# 02_HDMI_RX.net
KiCad netlist of a schematic drawn in Altium Designer
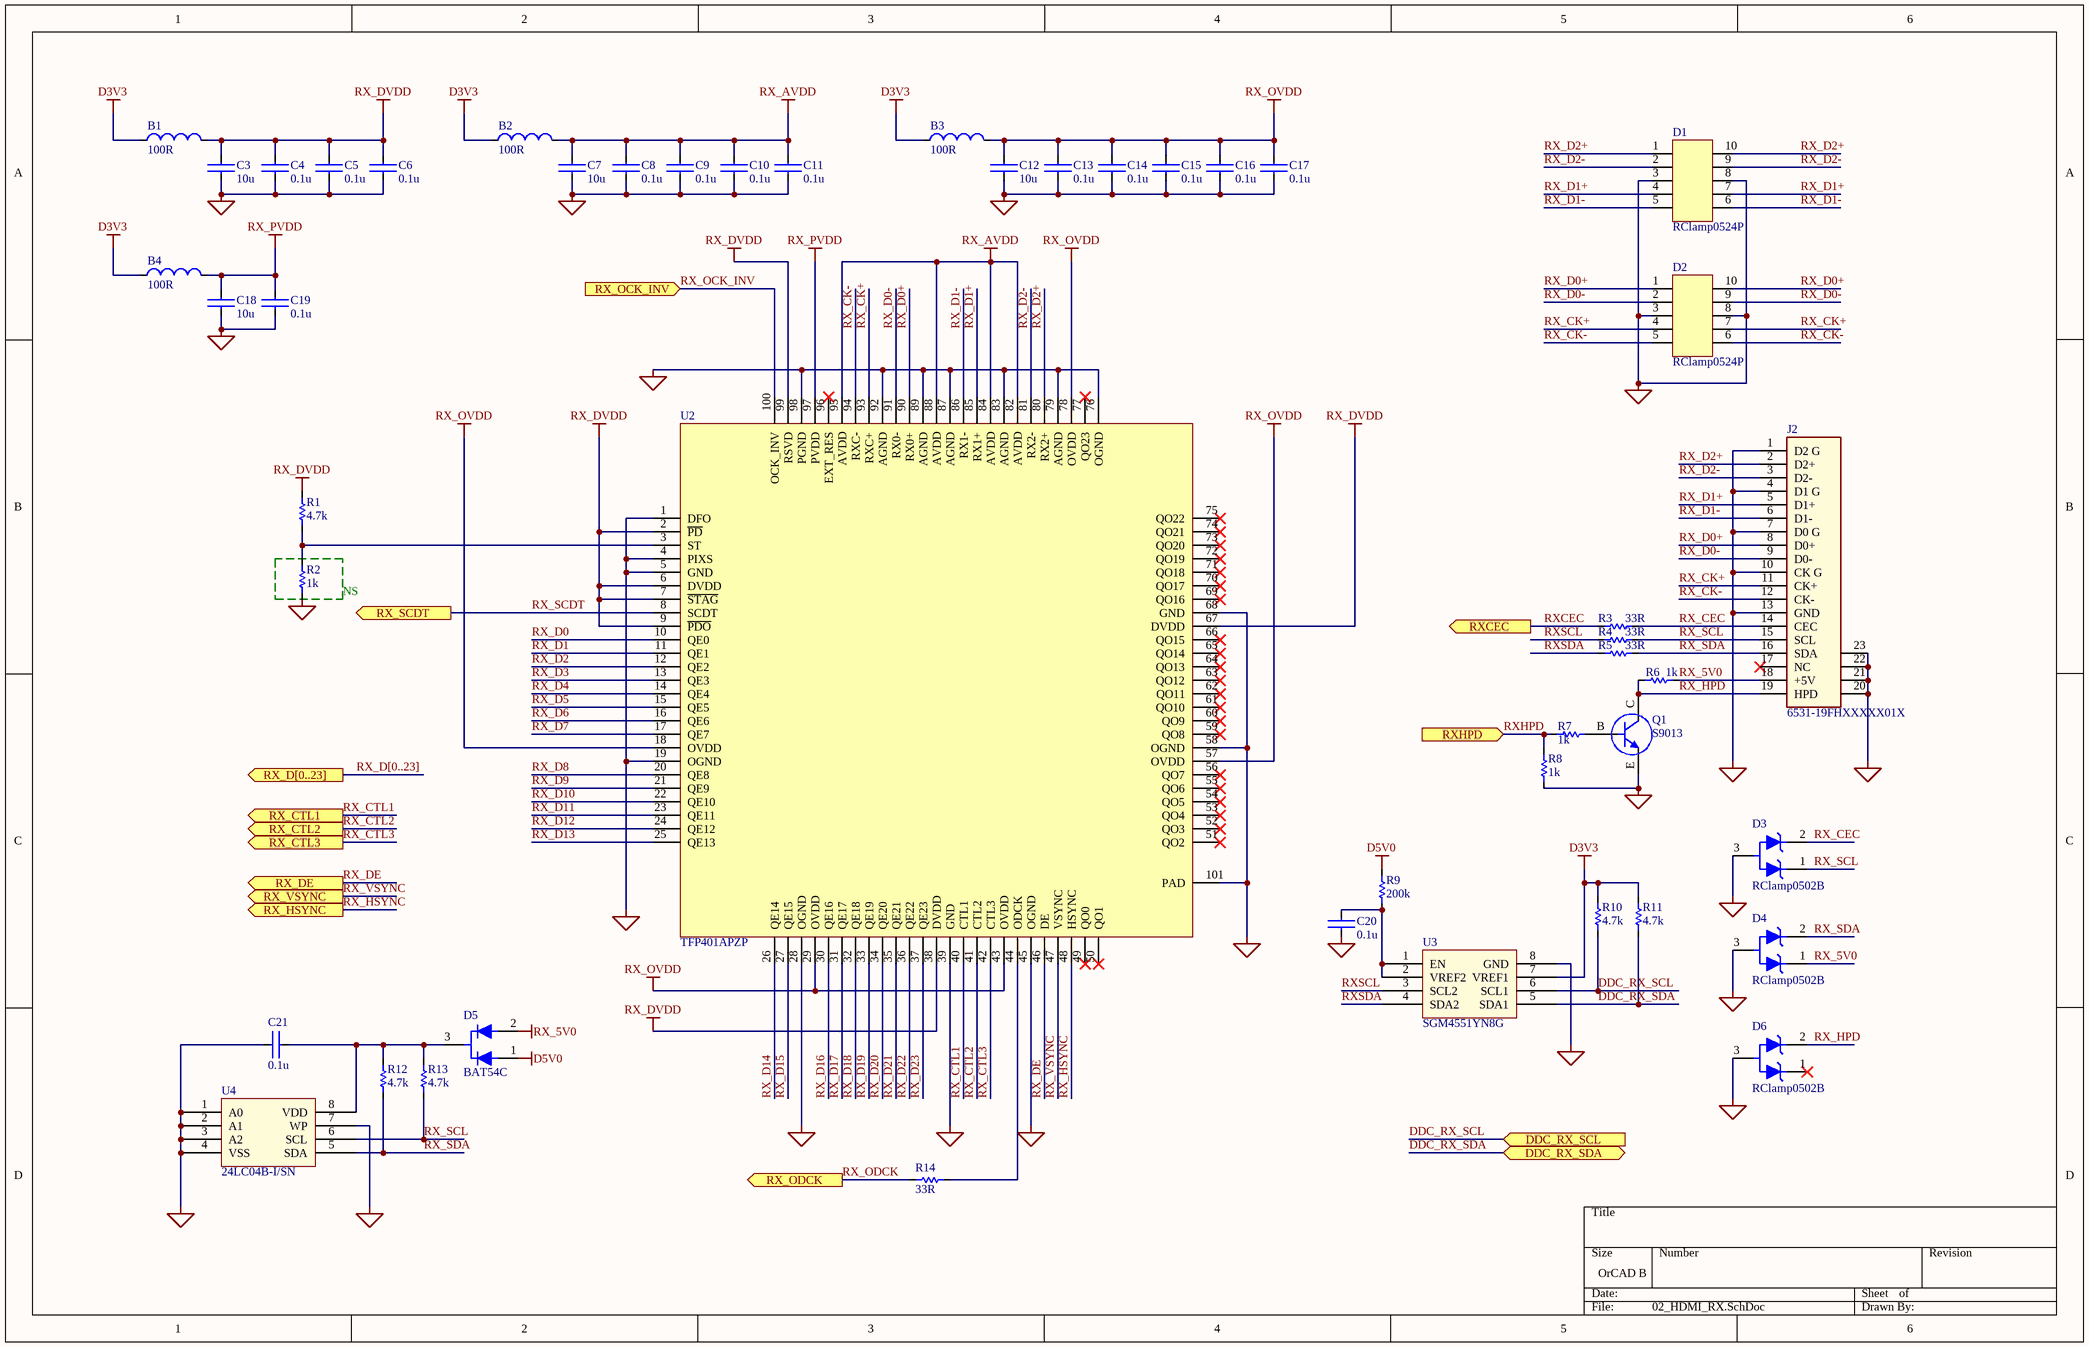
[diagram p0: 02_HDMI_RX.SchDoc]

(export (version "E")
  (design (tool "Eeschema 10.0.6"))
  (components
    (comp (ref "B1")
      (value "100R")
      (footprint "INDC1608X09N_B0603_TAIYO")
      (description "Bead,100R,2500mA,0.035ohm,0603")
      (libsource (lib "AD15_libpkg") (part "FBMH1608HM101-T"))
    )
    (comp (ref "B2")
      (value "100R")
      (footprint "INDC1608X09N_B0603_TAIYO")
      (description "Bead,100R,2500mA,0.035ohm,0603")
      (libsource (lib "AD15_libpkg") (part "FBMH1608HM101-T"))
    )
    (comp (ref "B3")
      (value "100R")
      (footprint "INDC1608X09N_B0603_TAIYO")
      (description "Bead,100R,2500mA,0.035ohm,0603")
      (libsource (lib "AD15_libpkg") (part "FBMH1608HM101-T"))
    )
    (comp (ref "B4")
      (value "100R")
      (footprint "INDC1608X09N_B0603_TAIYO")
      (description "Bead,100R,2500mA,0.035ohm,0603")
      (libsource (lib "AD15_libpkg") (part "FBMH1608HM101-T"))
    )
    (comp (ref "C3")
      (value "10u")
      (footprint "CAPC1608X09N_C0603")
      (description "CAP,Ceramic,X7R,10%,6.3V,10uF,0603")
      (libsource (lib "C0603") (part "CAP113"))
    )
    (comp (ref "C4")
      (value "0.1u")
      (footprint "C0402")
      (description "CAP,Ceramic,X7R,10%,16V,0.1uF,0402")
      (libsource (lib "C0402") (part "CAP011"))
    )
    (comp (ref "C5")
      (value "0.1u")
      (footprint "C0402")
      (description "CAP,Ceramic,X7R,10%,16V,0.1uF,0402")
      (libsource (lib "C0402") (part "CAP011"))
    )
    (comp (ref "C6")
      (value "0.1u")
      (footprint "C0402")
      (description "CAP,Ceramic,X7R,10%,16V,0.1uF,0402")
      (libsource (lib "C0402") (part "CAP011"))
    )
    (comp (ref "C7")
      (value "10u")
      (footprint "CAPC1608X09N_C0603")
      (description "CAP,Ceramic,X7R,10%,6.3V,10uF,0603")
      (libsource (lib "C0603") (part "CAP113"))
    )
    (comp (ref "C8")
      (value "0.1u")
      (footprint "C0402")
      (description "CAP,Ceramic,X7R,10%,16V,0.1uF,0402")
      (libsource (lib "C0402") (part "CAP011"))
    )
    (comp (ref "C9")
      (value "0.1u")
      (footprint "C0402")
      (description "CAP,Ceramic,X7R,10%,16V,0.1uF,0402")
      (libsource (lib "C0402") (part "CAP011"))
    )
    (comp (ref "C10")
      (value "0.1u")
      (footprint "C0402")
      (description "CAP,Ceramic,X7R,10%,16V,0.1uF,0402")
      (libsource (lib "C0402") (part "CAP011"))
    )
    (comp (ref "C11")
      (value "0.1u")
      (footprint "C0402")
      (description "CAP,Ceramic,X7R,10%,16V,0.1uF,0402")
      (libsource (lib "C0402") (part "CAP011"))
    )
    (comp (ref "C12")
      (value "10u")
      (footprint "CAPC1608X09N_C0603")
      (description "CAP,Ceramic,X7R,10%,6.3V,10uF,0603")
      (libsource (lib "C0603") (part "CAP113"))
    )
    (comp (ref "C13")
      (value "0.1u")
      (footprint "C0402")
      (description "CAP,Ceramic,X7R,10%,16V,0.1uF,0402")
      (libsource (lib "C0402") (part "CAP011"))
    )
    (comp (ref "C14")
      (value "0.1u")
      (footprint "C0402")
      (description "CAP,Ceramic,X7R,10%,16V,0.1uF,0402")
      (libsource (lib "C0402") (part "CAP011"))
    )
    (comp (ref "C15")
      (value "0.1u")
      (footprint "C0402")
      (description "CAP,Ceramic,X7R,10%,16V,0.1uF,0402")
      (libsource (lib "C0402") (part "CAP011"))
    )
    (comp (ref "C16")
      (value "0.1u")
      (footprint "C0402")
      (description "CAP,Ceramic,X7R,10%,16V,0.1uF,0402")
      (libsource (lib "C0402") (part "CAP011"))
    )
    (comp (ref "C17")
      (value "0.1u")
      (footprint "C0402")
      (description "CAP,Ceramic,X7R,10%,16V,0.1uF,0402")
      (libsource (lib "C0402") (part "CAP011"))
    )
    (comp (ref "C18")
      (value "10u")
      (footprint "CAPC1608X09N_C0603")
      (description "CAP,Ceramic,X7R,10%,6.3V,10uF,0603")
      (libsource (lib "C0603") (part "CAP113"))
    )
    (comp (ref "C19")
      (value "0.1u")
      (footprint "C0402")
      (description "CAP,Ceramic,X7R,10%,16V,0.1uF,0402")
      (libsource (lib "C0402") (part "CAP011"))
    )
    (comp (ref "C20")
      (value "0.1u")
      (footprint "C0402")
      (description "CAP,Ceramic,X7R,10%,16V,0.1uF,0402")
      (libsource (lib "C0402") (part "CAP011"))
    )
    (comp (ref "C21")
      (value "0.1u")
      (footprint "C0402")
      (description "CAP,Ceramic,X7R,10%,16V,0.1uF,0402")
      (libsource (lib "C0402") (part "CAP011"))
    )
    (comp (ref "D1")
      (value "RClamp0524P")
      (footprint "SLP2510P8_RClamp0524P")
      (description "TVS array,0.3pF,5V,SLP2510P8")
      (libsource (lib "AD15_libpkg") (part "RClamp0524P"))
    )
    (comp (ref "D2")
      (value "RClamp0524P")
      (footprint "SLP2510P8_RClamp0524P")
      (description "TVS array,0.3pF,5V,SLP2510P8")
      (libsource (lib "AD15_libpkg") (part "RClamp0524P"))
    )
    (comp (ref "D3")
      (value "RClamp0502B")
      (footprint "SOTFL50P160X90-3N_RClamp0502B")
      (description "TVS array,1pF,5V,SC75")
      (libsource (lib "AD15_libpkg") (part "RClamp0502B"))
    )
    (comp (ref "D4")
      (value "RClamp0502B")
      (footprint "SOTFL50P160X90-3N_RClamp0502B")
      (description "TVS array,1pF,5V,SC75")
      (libsource (lib "AD15_libpkg") (part "RClamp0502B"))
    )
    (comp (ref "D5")
      (value "BAT54C")
      (footprint "SOT95P230X110-3N_SOT23_BAT54")
      (description "Schottky Double Diodes,30V,200mA,SOT23,a1a2k1k2")
      (libsource (lib "AD15_libpkg") (part "BAT54C"))
    )
    (comp (ref "D6")
      (value "RClamp0502B")
      (footprint "SOTFL50P160X90-3N_RClamp0502B")
      (description "TVS array,1pF,5V,SC75")
      (libsource (lib "AD15_libpkg") (part "RClamp0502B"))
    )
    (comp (ref "J2")
      (value "6531-19FHXXXXX01X")
      (footprint "6531-19FHXXXXX01X")
      (description "Header,HDMI type C,19-Pin,Right angle,0.4mm Pitch,SMD")
      (libsource (lib "AD15_schlib") (part "6531-19FHXXXXX01X"))
    )
    (comp (ref "Q1")
      (value "S9013")
      (footprint "SOT95P240X115-3N_JCET_TRANSISTOR")
      (description "TRANSISTOR,NPN,40V,500mA,SOT23")
      (libsource (lib "AD15_libpkg") (part "S9013"))
    )
    (comp (ref "R1")
      (value "4.7k")
      (footprint "R0402")
      (description "RES,4.7k,1%,1/16W,0402")
      (libsource (lib "R0402") (part "RES015"))
    )
    (comp (ref "R2")
      (value "1k")
      (footprint "R0402")
      (description "RES,1k,1%,1/16W,0402")
      (libsource (lib "R0402") (part "RES011"))
    )
    (comp (ref "R3")
      (value "33R")
      (footprint "R0402")
      (description "RES,33R,1%,1/16W,0402")
      (libsource (lib "R0402") (part "RES017"))
    )
    (comp (ref "R4")
      (value "33R")
      (footprint "R0402")
      (description "RES,33R,1%,1/16W,0402")
      (libsource (lib "R0402") (part "RES017"))
    )
    (comp (ref "R5")
      (value "33R")
      (footprint "R0402")
      (description "RES,33R,1%,1/16W,0402")
      (libsource (lib "R0402") (part "RES017"))
    )
    (comp (ref "R6")
      (value "1k")
      (footprint "R0402")
      (description "RES,1k,1%,1/16W,0402")
      (libsource (lib "R0402") (part "RES011"))
    )
    (comp (ref "R7")
      (value "1k")
      (footprint "R0402")
      (description "RES,1k,1%,1/16W,0402")
      (libsource (lib "R0402") (part "RES011"))
    )
    (comp (ref "R8")
      (value "1k")
      (footprint "R0402")
      (description "RES,1k,1%,1/16W,0402")
      (libsource (lib "R0402") (part "RES011"))
    )
    (comp (ref "R9")
      (value "200k")
      (footprint "R0402")
      (description "RES,200k,1%,1/16W,0402")
      (libsource (lib "R0402") (part "RES0117"))
    )
    (comp (ref "R10")
      (value "4.7k")
      (footprint "R0402")
      (description "RES,4.7k,1%,1/16W,0402")
      (libsource (lib "R0402") (part "RES015"))
    )
    (comp (ref "R11")
      (value "4.7k")
      (footprint "R0402")
      (description "RES,4.7k,1%,1/16W,0402")
      (libsource (lib "R0402") (part "RES015"))
    )
    (comp (ref "R12")
      (value "4.7k")
      (footprint "R0402")
      (description "RES,4.7k,1%,1/16W,0402")
      (libsource (lib "R0402") (part "RES015"))
    )
    (comp (ref "R13")
      (value "4.7k")
      (footprint "R0402")
      (description "RES,4.7k,1%,1/16W,0402")
      (libsource (lib "R0402") (part "RES015"))
    )
    (comp (ref "R14")
      (value "33R")
      (footprint "R0402")
      (description "RES,33R,1%,1/16W,0402")
      (libsource (lib "R0402") (part "RES017"))
    )
    (comp (ref "U2")
      (value "TFP401APZP")
      (footprint "TSQFP50P1600X1600X120_HS-101N_TFP401")
      (description "IC,PanelBus Digital Receiver,HTQFP100")
      (libsource (lib "AD15_libpkg") (part "TFP401A"))
    )
    (comp (ref "U3")
      (value "SGM4551YN8G")
      (footprint "TSOP65P280X125-8N_SGM4551")
      (description "IC,I2C-bus and SMBus voltage-level translator,SOT23-8")
      (libsource (lib "AD15_libpkg") (part "SGM4551YN8G"))
    )
    (comp (ref "U4")
      (value "24LC04B-I/SN")
      (footprint "SOIC127P600X175-8N_24LC04B")
      (description "IC,EEPROM,512X8bits,I2C,SOIC8")
      (libsource (lib "AD15_libpkg") (part "24LC04B_01"))
    )
  )
  (nets
    (net (code "1") (name "/DDC_RX_SCL") (class "Default")
      (node (ref "R10") (pin "1") (pinfunction "0_1") (pintype "passive"))
      (node (ref "U3") (pin "6") (pinfunction "SCL1_6") (pintype "passive"))
    )
    (net (code "2") (name "/DDC_RX_SDA") (class "Default")
      (node (ref "R11") (pin "1") (pinfunction "0_1") (pintype "passive"))
      (node (ref "U3") (pin "5") (pinfunction "SDA1_5") (pintype "passive"))
    )
    (net (code "3") (name "/RXCEC") (class "Default")
      (node (ref "R3") (pin "1") (pinfunction "0_1") (pintype "passive"))
    )
    (net (code "4") (name "/RXHPD") (class "Default")
      (node (ref "R7") (pin "2") (pinfunction "2_2") (pintype "passive"))
      (node (ref "R8") (pin "2") (pinfunction "2_2") (pintype "passive"))
    )
    (net (code "5") (name "/RXSCL") (class "Default")
      (node (ref "R4") (pin "1") (pinfunction "0_1") (pintype "passive"))
      (node (ref "U3") (pin "3") (pinfunction "SCL2_3") (pintype "passive"))
    )
    (net (code "6") (name "/RXSDA") (class "Default")
      (node (ref "R5") (pin "1") (pinfunction "0_1") (pintype "passive"))
      (node (ref "U3") (pin "4") (pinfunction "SDA2_4") (pintype "passive"))
    )
    (net (code "7") (name "/RX_CEC") (class "Default")
      (node (ref "D3") (pin "2") (pinfunction "1_2") (pintype "passive"))
      (node (ref "J2") (pin "14") (pinfunction "CEC_14") (pintype "passive"))
      (node (ref "R3") (pin "2") (pinfunction "2_2") (pintype "passive"))
    )
    (net (code "8") (name "/RX_CK+") (class "Default")
      (node (ref "D2") (pin "4") (pinfunction "3_4") (pintype "passive"))
      (node (ref "D2") (pin "7") (pinfunction "6_7") (pintype "passive"))
      (node (ref "J2") (pin "11") (pinfunction "CK+_11") (pintype "passive"))
      (node (ref "U2") (pin "93") (pinfunction "RXC+_93") (pintype "passive"))
    )
    (net (code "9") (name "/RX_CK-") (class "Default")
      (node (ref "D2") (pin "5") (pinfunction "4_5") (pintype "passive"))
      (node (ref "D2") (pin "6") (pinfunction "5_6") (pintype "passive"))
      (node (ref "J2") (pin "12") (pinfunction "CK-_12") (pintype "passive"))
      (node (ref "U2") (pin "94") (pinfunction "RXC-_94") (pintype "passive"))
    )
    (net (code "10") (name "/RX_CTL1") (class "Default")
      (node (ref "U2") (pin "40") (pinfunction "CTL1_40") (pintype "passive"))
    )
    (net (code "11") (name "/RX_CTL2") (class "Default")
      (node (ref "U2") (pin "41") (pinfunction "CTL2_41") (pintype "passive"))
    )
    (net (code "12") (name "/RX_CTL3") (class "Default")
      (node (ref "U2") (pin "42") (pinfunction "CTL3_42") (pintype "passive"))
    )
    (net (code "13") (name "/RX_D0") (class "Default")
      (node (ref "U2") (pin "10") (pinfunction "QE0_10") (pintype "passive"))
    )
    (net (code "14") (name "/RX_D0+") (class "Default")
      (node (ref "D2") (pin "1") (pinfunction "0_1") (pintype "passive"))
      (node (ref "D2") (pin "10") (pinfunction "9_10") (pintype "passive"))
      (node (ref "J2") (pin "8") (pinfunction "D0+_8") (pintype "passive"))
      (node (ref "U2") (pin "90") (pinfunction "RX0+_90") (pintype "passive"))
    )
    (net (code "15") (name "/RX_D0-") (class "Default")
      (node (ref "D2") (pin "2") (pinfunction "1_2") (pintype "passive"))
      (node (ref "D2") (pin "9") (pinfunction "8_9") (pintype "passive"))
      (node (ref "J2") (pin "9") (pinfunction "D0-_9") (pintype "passive"))
      (node (ref "U2") (pin "91") (pinfunction "RX0-_91") (pintype "passive"))
    )
    (net (code "16") (name "/RX_D1") (class "Default")
      (node (ref "U2") (pin "11") (pinfunction "QE1_11") (pintype "passive"))
    )
    (net (code "17") (name "/RX_D1+") (class "Default")
      (node (ref "D1") (pin "4") (pinfunction "3_4") (pintype "passive"))
      (node (ref "D1") (pin "7") (pinfunction "6_7") (pintype "passive"))
      (node (ref "J2") (pin "5") (pinfunction "D1+_5") (pintype "passive"))
      (node (ref "U2") (pin "85") (pinfunction "RX1+_85") (pintype "passive"))
    )
    (net (code "18") (name "/RX_D1-") (class "Default")
      (node (ref "D1") (pin "5") (pinfunction "4_5") (pintype "passive"))
      (node (ref "D1") (pin "6") (pinfunction "5_6") (pintype "passive"))
      (node (ref "J2") (pin "6") (pinfunction "D1-_6") (pintype "passive"))
      (node (ref "U2") (pin "86") (pinfunction "RX1-_86") (pintype "passive"))
    )
    (net (code "19") (name "/RX_D2") (class "Default")
      (node (ref "U2") (pin "12") (pinfunction "QE2_12") (pintype "passive"))
    )
    (net (code "20") (name "/RX_D2+") (class "Default")
      (node (ref "D1") (pin "1") (pinfunction "0_1") (pintype "passive"))
      (node (ref "D1") (pin "10") (pinfunction "9_10") (pintype "passive"))
      (node (ref "J2") (pin "2") (pinfunction "D2+_2") (pintype "passive"))
      (node (ref "U2") (pin "80") (pinfunction "RX2+_80") (pintype "passive"))
    )
    (net (code "21") (name "/RX_D2-") (class "Default")
      (node (ref "D1") (pin "2") (pinfunction "1_2") (pintype "passive"))
      (node (ref "D1") (pin "9") (pinfunction "8_9") (pintype "passive"))
      (node (ref "J2") (pin "3") (pinfunction "D2-_3") (pintype "passive"))
      (node (ref "U2") (pin "81") (pinfunction "RX2-_81") (pintype "passive"))
    )
    (net (code "22") (name "/RX_D3") (class "Default")
      (node (ref "U2") (pin "13") (pinfunction "QE3_13") (pintype "passive"))
    )
    (net (code "23") (name "/RX_D4") (class "Default")
      (node (ref "U2") (pin "14") (pinfunction "QE4_14") (pintype "passive"))
    )
    (net (code "24") (name "/RX_D5") (class "Default")
      (node (ref "U2") (pin "15") (pinfunction "QE5_15") (pintype "passive"))
    )
    (net (code "25") (name "/RX_D6") (class "Default")
      (node (ref "U2") (pin "16") (pinfunction "QE6_16") (pintype "passive"))
    )
    (net (code "26") (name "/RX_D7") (class "Default")
      (node (ref "U2") (pin "17") (pinfunction "QE7_17") (pintype "passive"))
    )
    (net (code "27") (name "/RX_D8") (class "Default")
      (node (ref "U2") (pin "20") (pinfunction "QE8_20") (pintype "passive"))
    )
    (net (code "28") (name "/RX_D9") (class "Default")
      (node (ref "U2") (pin "21") (pinfunction "QE9_21") (pintype "passive"))
    )
    (net (code "29") (name "/RX_D10") (class "Default")
      (node (ref "U2") (pin "22") (pinfunction "QE10_22") (pintype "passive"))
    )
    (net (code "30") (name "/RX_D11") (class "Default")
      (node (ref "U2") (pin "23") (pinfunction "QE11_23") (pintype "passive"))
    )
    (net (code "31") (name "/RX_D12") (class "Default")
      (node (ref "U2") (pin "24") (pinfunction "QE12_24") (pintype "passive"))
    )
    (net (code "32") (name "/RX_D13") (class "Default")
      (node (ref "U2") (pin "25") (pinfunction "QE13_25") (pintype "passive"))
    )
    (net (code "33") (name "/RX_D14") (class "Default")
      (node (ref "U2") (pin "26") (pinfunction "QE14_26") (pintype "passive"))
    )
    (net (code "34") (name "/RX_D15") (class "Default")
      (node (ref "U2") (pin "27") (pinfunction "QE15_27") (pintype "passive"))
    )
    (net (code "35") (name "/RX_D16") (class "Default")
      (node (ref "U2") (pin "30") (pinfunction "QE16_30") (pintype "passive"))
    )
    (net (code "36") (name "/RX_D17") (class "Default")
      (node (ref "U2") (pin "31") (pinfunction "QE17_31") (pintype "passive"))
    )
    (net (code "37") (name "/RX_D18") (class "Default")
      (node (ref "U2") (pin "32") (pinfunction "QE18_32") (pintype "passive"))
    )
    (net (code "38") (name "/RX_D19") (class "Default")
      (node (ref "U2") (pin "33") (pinfunction "QE19_33") (pintype "passive"))
    )
    (net (code "39") (name "/RX_D20") (class "Default")
      (node (ref "U2") (pin "34") (pinfunction "QE20_34") (pintype "passive"))
    )
    (net (code "40") (name "/RX_D21") (class "Default")
      (node (ref "U2") (pin "35") (pinfunction "QE21_35") (pintype "passive"))
    )
    (net (code "41") (name "/RX_D22") (class "Default")
      (node (ref "U2") (pin "36") (pinfunction "QE22_36") (pintype "passive"))
    )
    (net (code "42") (name "/RX_D23") (class "Default")
      (node (ref "U2") (pin "37") (pinfunction "QE23_37") (pintype "passive"))
    )
    (net (code "43") (name "/RX_DE") (class "Default")
      (node (ref "U2") (pin "46") (pinfunction "DE_46") (pintype "passive"))
    )
    (net (code "45") (name "/RX_HPD") (class "Default")
      (node (ref "D6") (pin "2") (pinfunction "1_2") (pintype "passive"))
      (node (ref "J2") (pin "19") (pinfunction "HPD_19") (pintype "passive"))
      (node (ref "Q1") (pin "C") (pinfunction "C_C") (pintype "passive"))
      (node (ref "R6") (pin "2") (pinfunction "2_2") (pintype "passive"))
    )
    (net (code "46") (name "/RX_HSYNC") (class "Default")
      (node (ref "U2") (pin "48") (pinfunction "HSYNC_48") (pintype "passive"))
    )
    (net (code "47") (name "/RX_OCK_INV") (class "Default")
      (node (ref "U2") (pin "100") (pinfunction "OCK_INV_100") (pintype "passive"))
    )
    (net (code "48") (name "/RX_ODCK") (class "Default")
      (node (ref "R14") (pin "1") (pinfunction "0_1") (pintype "passive"))
    )
    (net (code "49") (name "/RX_SCDT") (class "Default")
      (node (ref "U2") (pin "8") (pinfunction "SCDT_8") (pintype "passive"))
    )
    (net (code "50") (name "/RX_SCL") (class "Default")
      (node (ref "D3") (pin "1") (pinfunction "0_1") (pintype "passive"))
      (node (ref "J2") (pin "15") (pinfunction "SCL_15") (pintype "passive"))
      (node (ref "R13") (pin "1") (pinfunction "0_1") (pintype "passive"))
      (node (ref "R4") (pin "2") (pinfunction "2_2") (pintype "passive"))
      (node (ref "U4") (pin "6") (pinfunction "SCL_6") (pintype "passive"))
    )
    (net (code "51") (name "/RX_SDA") (class "Default")
      (node (ref "D4") (pin "2") (pinfunction "1_2") (pintype "passive"))
      (node (ref "J2") (pin "16") (pinfunction "SDA_16") (pintype "passive"))
      (node (ref "R12") (pin "1") (pinfunction "0_1") (pintype "passive"))
      (node (ref "R5") (pin "2") (pinfunction "2_2") (pintype "passive"))
      (node (ref "U4") (pin "5") (pinfunction "SDA_5") (pintype "passive"))
    )
    (net (code "52") (name "/RX_VSYNC") (class "Default")
      (node (ref "U2") (pin "47") (pinfunction "VSYNC_47") (pintype "passive"))
    )
    (net (code "53") (name "D3V3") (class "Default")
      (node (ref "B1") (pin "2") (pinfunction "1_2") (pintype "passive"))
      (node (ref "B2") (pin "2") (pinfunction "1_2") (pintype "passive"))
      (node (ref "B3") (pin "2") (pinfunction "1_2") (pintype "passive"))
      (node (ref "B4") (pin "2") (pinfunction "1_2") (pintype "passive"))
      (node (ref "R10") (pin "2") (pinfunction "2_2") (pintype "passive"))
      (node (ref "R11") (pin "2") (pinfunction "2_2") (pintype "passive"))
      (node (ref "U3") (pin "7") (pinfunction "VREF1_7") (pintype "passive"))
    )
    (net (code "54") (name "D5V0") (class "Default")
      (node (ref "D5") (pin "1") (pinfunction "0_1") (pintype "passive"))
      (node (ref "R9") (pin "2") (pinfunction "2_2") (pintype "passive"))
    )
    (net (code "55") (name "GND") (class "Default")
      (node (ref "C10") (pin "2") (pinfunction "1_2") (pintype "passive"))
      (node (ref "C11") (pin "2") (pinfunction "1_2") (pintype "passive"))
      (node (ref "C12") (pin "2") (pinfunction "1_2") (pintype "passive"))
      (node (ref "C13") (pin "2") (pinfunction "1_2") (pintype "passive"))
      (node (ref "C14") (pin "2") (pinfunction "1_2") (pintype "passive"))
      (node (ref "C15") (pin "2") (pinfunction "1_2") (pintype "passive"))
      (node (ref "C16") (pin "2") (pinfunction "1_2") (pintype "passive"))
      (node (ref "C17") (pin "2") (pinfunction "1_2") (pintype "passive"))
      (node (ref "C18") (pin "2") (pinfunction "1_2") (pintype "passive"))
      (node (ref "C19") (pin "2") (pinfunction "1_2") (pintype "passive"))
      (node (ref "C20") (pin "2") (pinfunction "1_2") (pintype "passive"))
      (node (ref "C21") (pin "1") (pinfunction "0_1") (pintype "passive"))
      (node (ref "C3") (pin "2") (pinfunction "1_2") (pintype "passive"))
      (node (ref "C4") (pin "2") (pinfunction "1_2") (pintype "passive"))
      (node (ref "C5") (pin "2") (pinfunction "1_2") (pintype "passive"))
      (node (ref "C6") (pin "2") (pinfunction "1_2") (pintype "passive"))
      (node (ref "C7") (pin "2") (pinfunction "1_2") (pintype "passive"))
      (node (ref "C8") (pin "2") (pinfunction "1_2") (pintype "passive"))
      (node (ref "C9") (pin "2") (pinfunction "1_2") (pintype "passive"))
      (node (ref "D1") (pin "3") (pinfunction "2_3") (pintype "passive"))
      (node (ref "D1") (pin "8") (pinfunction "7_8") (pintype "passive"))
      (node (ref "D2") (pin "3") (pinfunction "2_3") (pintype "passive"))
      (node (ref "D2") (pin "8") (pinfunction "7_8") (pintype "passive"))
      (node (ref "D3") (pin "3") (pinfunction "2_3") (pintype "passive"))
      (node (ref "D4") (pin "3") (pinfunction "2_3") (pintype "passive"))
      (node (ref "D6") (pin "3") (pinfunction "2_3") (pintype "passive"))
      (node (ref "J2") (pin "1") (pinfunction "D2_G_1") (pintype "passive"))
      (node (ref "J2") (pin "10") (pinfunction "CK_G_10") (pintype "passive"))
      (node (ref "J2") (pin "13") (pinfunction "GND_13") (pintype "passive"))
      (node (ref "J2") (pin "20") (pinfunction "3_20") (pintype "passive"))
      (node (ref "J2") (pin "21") (pinfunction "4_21") (pintype "passive"))
      (node (ref "J2") (pin "22") (pinfunction "5_22") (pintype "passive"))
      (node (ref "J2") (pin "23") (pinfunction "6_23") (pintype "passive"))
      (node (ref "J2") (pin "4") (pinfunction "D1_G_4") (pintype "passive"))
      (node (ref "J2") (pin "7") (pinfunction "D0_G_7") (pintype "passive"))
      (node (ref "Q1") (pin "E") (pinfunction "E_E") (pintype "passive"))
      (node (ref "R2") (pin "1") (pinfunction "0_1") (pintype "passive"))
      (node (ref "R8") (pin "1") (pinfunction "0_1") (pintype "passive"))
      (node (ref "U2") (pin "1") (pinfunction "DFO_1") (pintype "passive"))
      (node (ref "U2") (pin "101") (pinfunction "PAD_101") (pintype "passive"))
      (node (ref "U2") (pin "19") (pinfunction "OGND_19") (pintype "passive"))
      (node (ref "U2") (pin "28") (pinfunction "OGND_28") (pintype "passive"))
      (node (ref "U2") (pin "39") (pinfunction "GND_39") (pintype "passive"))
      (node (ref "U2") (pin "4") (pinfunction "PIXS_4") (pintype "passive"))
      (node (ref "U2") (pin "45") (pinfunction "OGND_45") (pintype "passive"))
      (node (ref "U2") (pin "5") (pinfunction "GND_5") (pintype "passive"))
      (node (ref "U2") (pin "58") (pinfunction "OGND_58") (pintype "passive"))
      (node (ref "U2") (pin "68") (pinfunction "GND_68") (pintype "passive"))
      (node (ref "U2") (pin "76") (pinfunction "OGND_76") (pintype "passive"))
      (node (ref "U2") (pin "79") (pinfunction "AGND_79") (pintype "passive"))
      (node (ref "U2") (pin "83") (pinfunction "AGND_83") (pintype "passive"))
      (node (ref "U2") (pin "87") (pinfunction "AGND_87") (pintype "passive"))
      (node (ref "U2") (pin "89") (pinfunction "AGND_89") (pintype "passive"))
      (node (ref "U2") (pin "92") (pinfunction "AGND_92") (pintype "passive"))
      (node (ref "U2") (pin "98") (pinfunction "PGND_98") (pintype "passive"))
      (node (ref "U3") (pin "8") (pinfunction "GND_8") (pintype "passive"))
      (node (ref "U4") (pin "1") (pinfunction "A0_1") (pintype "passive"))
      (node (ref "U4") (pin "2") (pinfunction "A1_2") (pintype "passive"))
      (node (ref "U4") (pin "3") (pinfunction "A2_3") (pintype "passive"))
      (node (ref "U4") (pin "4") (pinfunction "VSS_4") (pintype "passive"))
      (node (ref "U4") (pin "7") (pinfunction "WP_7") (pintype "passive"))
    )
    (net (code "56") (name "Net-(C20-0)") (class "Default")
      (node (ref "C20") (pin "1") (pinfunction "0_1") (pintype "passive"))
      (node (ref "R9") (pin "1") (pinfunction "0_1") (pintype "passive"))
      (node (ref "U3") (pin "1") (pinfunction "EN_1") (pintype "passive"))
      (node (ref "U3") (pin "2") (pinfunction "VREF2_2") (pintype "passive"))
    )
    (net (code "57") (name "Net-(C21-1)") (class "Default")
      (node (ref "C21") (pin "2") (pinfunction "1_2") (pintype "passive"))
      (node (ref "D5") (pin "3") (pinfunction "2_3") (pintype "passive"))
      (node (ref "R12") (pin "2") (pinfunction "2_2") (pintype "passive"))
      (node (ref "R13") (pin "2") (pinfunction "2_2") (pintype "passive"))
      (node (ref "U4") (pin "8") (pinfunction "VDD_8") (pintype "passive"))
    )
    (net (code "58") (name "Net-(R1-0)") (class "Default")
      (node (ref "R1") (pin "1") (pinfunction "0_1") (pintype "passive"))
      (node (ref "R2") (pin "2") (pinfunction "2_2") (pintype "passive"))
      (node (ref "U2") (pin "3") (pinfunction "ST_3") (pintype "passive"))
    )
    (net (code "59") (name "Net-(R7-0)") (class "Default")
      (node (ref "Q1") (pin "B") (pinfunction "B_B") (pintype "passive"))
      (node (ref "R7") (pin "1") (pinfunction "0_1") (pintype "passive"))
    )
    (net (code "60") (name "Net-(U2-ODCK)") (class "Default")
      (node (ref "R14") (pin "2") (pinfunction "2_2") (pintype "passive"))
      (node (ref "U2") (pin "44") (pinfunction "ODCK_44") (pintype "passive"))
    )
    (net (code "61") (name "RX_5V0") (class "Default")
      (node (ref "D4") (pin "1") (pinfunction "0_1") (pintype "passive"))
      (node (ref "D5") (pin "2") (pinfunction "1_2") (pintype "passive"))
      (node (ref "J2") (pin "18") (pinfunction "+5V_18") (pintype "passive"))
      (node (ref "R6") (pin "1") (pinfunction "0_1") (pintype "passive"))
    )
    (net (code "62") (name "RX_AVDD") (class "Default")
      (node (ref "B2") (pin "1") (pinfunction "0_1") (pintype "passive"))
      (node (ref "C10") (pin "1") (pinfunction "0_1") (pintype "passive"))
      (node (ref "C11") (pin "1") (pinfunction "0_1") (pintype "passive"))
      (node (ref "C7") (pin "1") (pinfunction "0_1") (pintype "passive"))
      (node (ref "C8") (pin "1") (pinfunction "0_1") (pintype "passive"))
      (node (ref "C9") (pin "1") (pinfunction "0_1") (pintype "passive"))
      (node (ref "U2") (pin "82") (pinfunction "AVDD_82") (pintype "passive"))
      (node (ref "U2") (pin "84") (pinfunction "AVDD_84") (pintype "passive"))
      (node (ref "U2") (pin "88") (pinfunction "AVDD_88") (pintype "passive"))
      (node (ref "U2") (pin "95") (pinfunction "AVDD_95") (pintype "passive"))
    )
    (net (code "63") (name "RX_DVDD") (class "Default")
      (node (ref "B1") (pin "1") (pinfunction "0_1") (pintype "passive"))
      (node (ref "C3") (pin "1") (pinfunction "0_1") (pintype "passive"))
      (node (ref "C4") (pin "1") (pinfunction "0_1") (pintype "passive"))
      (node (ref "C5") (pin "1") (pinfunction "0_1") (pintype "passive"))
      (node (ref "C6") (pin "1") (pinfunction "0_1") (pintype "passive"))
      (node (ref "R1") (pin "2") (pinfunction "2_2") (pintype "passive"))
      (node (ref "U2") (pin "2") (pinfunction "~{PD}_2") (pintype "passive"))
      (node (ref "U2") (pin "38") (pinfunction "DVDD_38") (pintype "passive"))
      (node (ref "U2") (pin "6") (pinfunction "DVDD_6") (pintype "passive"))
      (node (ref "U2") (pin "67") (pinfunction "DVDD_67") (pintype "passive"))
      (node (ref "U2") (pin "7") (pinfunction "~{STAG}_7") (pintype "passive"))
      (node (ref "U2") (pin "9") (pinfunction "~{PDO}_9") (pintype "passive"))
      (node (ref "U2") (pin "99") (pinfunction "RSVD_99") (pintype "passive"))
    )
    (net (code "64") (name "RX_OVDD") (class "Default")
      (node (ref "B3") (pin "1") (pinfunction "0_1") (pintype "passive"))
      (node (ref "C12") (pin "1") (pinfunction "0_1") (pintype "passive"))
      (node (ref "C13") (pin "1") (pinfunction "0_1") (pintype "passive"))
      (node (ref "C14") (pin "1") (pinfunction "0_1") (pintype "passive"))
      (node (ref "C15") (pin "1") (pinfunction "0_1") (pintype "passive"))
      (node (ref "C16") (pin "1") (pinfunction "0_1") (pintype "passive"))
      (node (ref "C17") (pin "1") (pinfunction "0_1") (pintype "passive"))
      (node (ref "U2") (pin "18") (pinfunction "OVDD_18") (pintype "passive"))
      (node (ref "U2") (pin "29") (pinfunction "OVDD_29") (pintype "passive"))
      (node (ref "U2") (pin "43") (pinfunction "OVDD_43") (pintype "passive"))
      (node (ref "U2") (pin "57") (pinfunction "OVDD_57") (pintype "passive"))
      (node (ref "U2") (pin "78") (pinfunction "OVDD_78") (pintype "passive"))
    )
    (net (code "65") (name "RX_PVDD") (class "Default")
      (node (ref "B4") (pin "1") (pinfunction "0_1") (pintype "passive"))
      (node (ref "C18") (pin "1") (pinfunction "0_1") (pintype "passive"))
      (node (ref "C19") (pin "1") (pinfunction "0_1") (pintype "passive"))
      (node (ref "U2") (pin "97") (pinfunction "PVDD_97") (pintype "passive"))
    )
    (net (code "66") (name "unconnected-(D6-0-Pad1)") (class "Default")
      (node (ref "D6") (pin "1") (pinfunction "0_1") (pintype "passive+no_connect"))
    )
    (net (code "67") (name "unconnected-(J2-NC-Pad17)") (class "Default")
      (node (ref "J2") (pin "17") (pinfunction "NC_17") (pintype "passive+no_connect"))
    )
    (net (code "68") (name "unconnected-(U2-EXT_RES-Pad96)") (class "Default")
      (node (ref "U2") (pin "96") (pinfunction "EXT_RES_96") (pintype "passive+no_connect"))
    )
    (net (code "69") (name "unconnected-(U2-QO0-Pad49)") (class "Default")
      (node (ref "U2") (pin "49") (pinfunction "QO0_49") (pintype "passive+no_connect"))
    )
    (net (code "70") (name "unconnected-(U2-QO1-Pad50)") (class "Default")
      (node (ref "U2") (pin "50") (pinfunction "QO1_50") (pintype "passive+no_connect"))
    )
    (net (code "71") (name "unconnected-(U2-QO2-Pad51)") (class "Default")
      (node (ref "U2") (pin "51") (pinfunction "QO2_51") (pintype "passive+no_connect"))
    )
    (net (code "72") (name "unconnected-(U2-QO3-Pad52)") (class "Default")
      (node (ref "U2") (pin "52") (pinfunction "QO3_52") (pintype "passive+no_connect"))
    )
    (net (code "73") (name "unconnected-(U2-QO4-Pad53)") (class "Default")
      (node (ref "U2") (pin "53") (pinfunction "QO4_53") (pintype "passive+no_connect"))
    )
    (net (code "74") (name "unconnected-(U2-QO5-Pad54)") (class "Default")
      (node (ref "U2") (pin "54") (pinfunction "QO5_54") (pintype "passive+no_connect"))
    )
    (net (code "75") (name "unconnected-(U2-QO6-Pad55)") (class "Default")
      (node (ref "U2") (pin "55") (pinfunction "QO6_55") (pintype "passive+no_connect"))
    )
    (net (code "76") (name "unconnected-(U2-QO7-Pad56)") (class "Default")
      (node (ref "U2") (pin "56") (pinfunction "QO7_56") (pintype "passive+no_connect"))
    )
    (net (code "77") (name "unconnected-(U2-QO8-Pad59)") (class "Default")
      (node (ref "U2") (pin "59") (pinfunction "QO8_59") (pintype "passive+no_connect"))
    )
    (net (code "78") (name "unconnected-(U2-QO9-Pad60)") (class "Default")
      (node (ref "U2") (pin "60") (pinfunction "QO9_60") (pintype "passive+no_connect"))
    )
    (net (code "79") (name "unconnected-(U2-QO10-Pad61)") (class "Default")
      (node (ref "U2") (pin "61") (pinfunction "QO10_61") (pintype "passive+no_connect"))
    )
    (net (code "80") (name "unconnected-(U2-QO11-Pad62)") (class "Default")
      (node (ref "U2") (pin "62") (pinfunction "QO11_62") (pintype "passive+no_connect"))
    )
    (net (code "81") (name "unconnected-(U2-QO12-Pad63)") (class "Default")
      (node (ref "U2") (pin "63") (pinfunction "QO12_63") (pintype "passive+no_connect"))
    )
    (net (code "82") (name "unconnected-(U2-QO13-Pad64)") (class "Default")
      (node (ref "U2") (pin "64") (pinfunction "QO13_64") (pintype "passive+no_connect"))
    )
    (net (code "83") (name "unconnected-(U2-QO14-Pad65)") (class "Default")
      (node (ref "U2") (pin "65") (pinfunction "QO14_65") (pintype "passive+no_connect"))
    )
    (net (code "84") (name "unconnected-(U2-QO15-Pad66)") (class "Default")
      (node (ref "U2") (pin "66") (pinfunction "QO15_66") (pintype "passive+no_connect"))
    )
    (net (code "85") (name "unconnected-(U2-QO16-Pad69)") (class "Default")
      (node (ref "U2") (pin "69") (pinfunction "QO16_69") (pintype "passive+no_connect"))
    )
    (net (code "86") (name "unconnected-(U2-QO17-Pad70)") (class "Default")
      (node (ref "U2") (pin "70") (pinfunction "QO17_70") (pintype "passive+no_connect"))
    )
    (net (code "87") (name "unconnected-(U2-QO18-Pad71)") (class "Default")
      (node (ref "U2") (pin "71") (pinfunction "QO18_71") (pintype "passive+no_connect"))
    )
    (net (code "88") (name "unconnected-(U2-QO19-Pad72)") (class "Default")
      (node (ref "U2") (pin "72") (pinfunction "QO19_72") (pintype "passive+no_connect"))
    )
    (net (code "89") (name "unconnected-(U2-QO20-Pad73)") (class "Default")
      (node (ref "U2") (pin "73") (pinfunction "QO20_73") (pintype "passive+no_connect"))
    )
    (net (code "90") (name "unconnected-(U2-QO21-Pad74)") (class "Default")
      (node (ref "U2") (pin "74") (pinfunction "QO21_74") (pintype "passive+no_connect"))
    )
    (net (code "91") (name "unconnected-(U2-QO22-Pad75)") (class "Default")
      (node (ref "U2") (pin "75") (pinfunction "QO22_75") (pintype "passive+no_connect"))
    )
    (net (code "92") (name "unconnected-(U2-QO23-Pad77)") (class "Default")
      (node (ref "U2") (pin "77") (pinfunction "QO23_77") (pintype "passive+no_connect"))
    )
  )
)
